# USB_SERIAL.net
KiCad netlist of a schematic drawn in Altium Designer
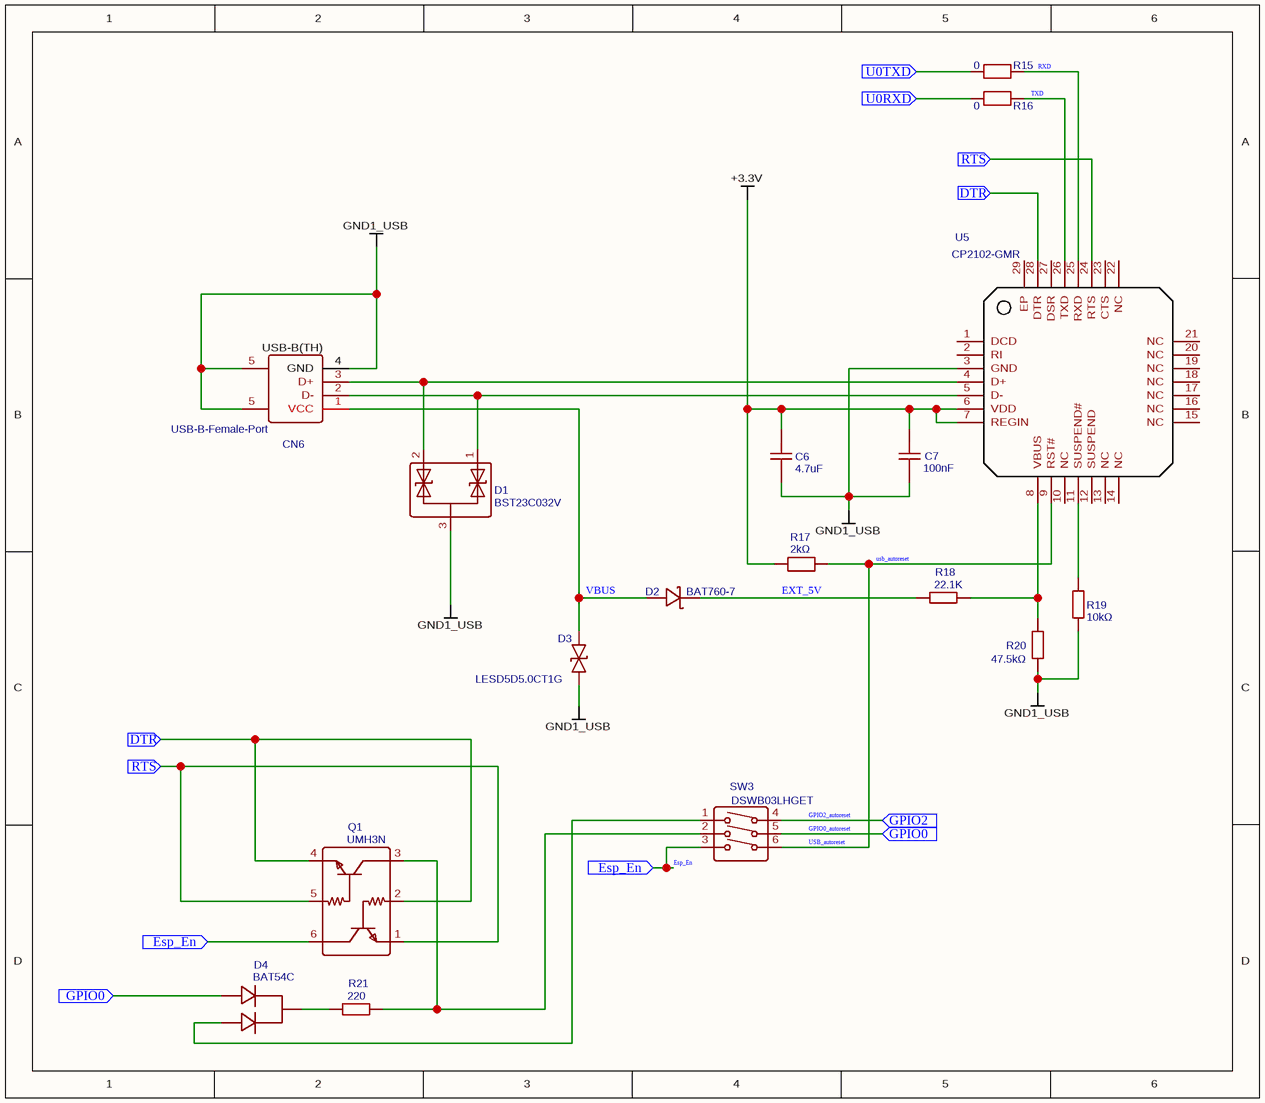
[diagram p0: USB_SERIAL.schdoc]

(export (version "E")
  (design (tool "Eeschema 10.0.6"))
  (components
    (comp (ref "C6")
      (value "4.7uF")
      (fields
        (field (name "BOM_SUPPLIER PART") "C140692")
        (field (name "BOM_MANUFACTURER PART") "CL21A475KQFNNNE")
        (field (name "CONTRIBUTOR") "LCSC")
      )
      (libsource (lib "altium-import") (part "root_1_4.7uF_"))
    )
    (comp (ref "C7")
      (value "100nF")
      (fields
        (field (name "BOM_SUPPLIER PART") "C519981")
        (field (name "BOM_MANUFACTURER PART") "CC0805KRX7R8BB104")
        (field (name "CONTRIBUTOR") "LCSC")
      )
      (libsource (lib "altium-import") (part "root_1_100nF_"))
    )
    (comp (ref "CN6")
      (value "USB-B-Female-Port")
      (fields
        (field (name "BOM_MANUFACTURER PART") "921-112A1010D10200")
        (field (name "BOM_SUPPLIER PART") "C46393")
      )
      (libsource (lib "altium-import") (part "root_0_USB-B-Female-Port_"))
    )
    (comp (ref "D1")
      (value "BST23C032V")
      (fields (field (name "BOM_SUPPLIER PART") "C151968") (field (name "CONTRIBUTOR") "LCSC"))
      (libsource (lib "altium-import") (part "root_2_BST23C032V_"))
    )
    (comp (ref "D2")
      (value "BAT760-7")
      (fields (field (name "BOM_SUPPLIER PART") "C124187") (field (name "CONTRIBUTOR") "LCSC"))
      (libsource (lib "altium-import") (part "root_2_BAT760-7_"))
    )
    (comp (ref "D3")
      (value "LESD5D5.0CT1G")
      (fields (field (name "BOM_SUPPLIER PART") "C383211") (field (name "CONTRIBUTOR") "LCSC"))
      (libsource (lib "altium-import") (part "root_1_LESD5D5.0CT1G_"))
    )
    (comp (ref "D4")
      (value "BAT54C")
      (fields (field (name "BOM_SUPPLIER PART") "C2135"))
      (libsource (lib "altium-import") (part "root_0_BAT54C_"))
    )
    (comp (ref "Q1")
      (value "UMH3N")
      (fields (field (name "BOM_SUPPLIER PART") "C62892"))
      (libsource (lib "altium-import") (part "root_1_UMH3N_"))
    )
    (comp (ref "R15")
      (value "0")
      (fields
        (field (name "BOM_SUPPLIER PART") "C174076")
        (field (name "BOM_MANUFACTURER PART") "AC0805FR-070RL")
        (field (name "CONTRIBUTOR") "LCSC")
      )
      (libsource (lib "altium-import") (part "root_0_0_"))
    )
    (comp (ref "R16")
      (value "0")
      (fields
        (field (name "BOM_SUPPLIER PART") "C174076")
        (field (name "BOM_MANUFACTURER PART") "AC0805FR-070RL")
        (field (name "CONTRIBUTOR") "LCSC")
      )
      (libsource (lib "altium-import") (part "root_0_0_"))
    )
    (comp (ref "R17")
      (value "2kΩ")
      (fields
        (field (name "BOM_SUPPLIER PART") "C479096")
        (field (name "BOM_MANUFACTURER PART") "PTFR0805B2K00P9")
        (field (name "CONTRIBUTOR") "LCSC")
      )
      (libsource (lib "altium-import") (part "root_0_2kΩ_"))
    )
    (comp (ref "R18")
      (value "22.1K")
      (fields
        (field (name "BOM_SUPPLIER PART") "C204311")
        (field (name "BOM_MANUFACTURER PART") "CR0805-FX-2212ELF")
        (field (name "CONTRIBUTOR") "LCSC")
      )
      (libsource (lib "altium-import") (part "root_0_22.1K_"))
    )
    (comp (ref "R19")
      (value "10kΩ")
      (fields
        (field (name "BOM_SUPPLIER PART") "C332266")
        (field (name "BOM_MANUFACTURER PART") "TR0805D10KP0550")
        (field (name "CONTRIBUTOR") "LCSC")
      )
      (libsource (lib "altium-import") (part "root_1_10kΩ_"))
    )
    (comp (ref "R20")
      (value "47.5kΩ")
      (fields
        (field (name "BOM_SUPPLIER PART") "C79481")
        (field (name "BOM_MANUFACTURER PART") "TC0525B4752T5E")
        (field (name "CONTRIBUTOR") "LCSC")
      )
      (libsource (lib "altium-import") (part "root_1_47.5kΩ_"))
    )
    (comp (ref "R21")
      (value "220")
      (fields
        (field (name "BOM_MANUFACTURER PART") "RC0805JR-7W220RL")
        (field (name "BOM_SUPPLIER PART") "C163392")
        (field (name "CONTRIBUTOR") "LCSC")
      )
      (libsource (lib "altium-import") (part "root_2_220_"))
    )
    (comp (ref "SW3")
      (value "DSWB03LHGET")
      (fields (field (name "BOM_SUPPLIER PART") "C99420") (field (name "CONTRIBUTOR") "LCSC"))
      (libsource (lib "altium-import") (part "root_3_DSWB03LHGET_"))
    )
    (comp (ref "U5")
      (value "CP2102-GMR")
      (fields (field (name "BOM_SUPPLIER PART") "C6568"))
      (libsource (lib "altium-import") (part "root_0_CP2102-GMR_"))
    )
  )
  (nets
    (net (code "1") (name "+3.3V") (class "Default")
      (node (ref "C6") (pin "2") (pinfunction "2_2") (pintype "passive"))
      (node (ref "C7") (pin "2") (pinfunction "2_2") (pintype "passive"))
      (node (ref "R17") (pin "1") (pinfunction "1_1") (pintype "passive"))
      (node (ref "U5") (pin "6") (pinfunction "VDD_6") (pintype "passive"))
      (node (ref "U5") (pin "7") (pinfunction "REGIN_7") (pintype "passive"))
    )
    (net (code "2") (name "/DTR") (class "Default")
      (node (ref "Q1") (pin "2") (pinfunction "B_2") (pintype "passive"))
      (node (ref "Q1") (pin "4") (pinfunction "E_4") (pintype "passive"))
      (node (ref "U5") (pin "28") (pinfunction "DTR_28") (pintype "passive"))
    )
    (net (code "3") (name "/EXT_5V") (class "Default")
      (node (ref "D2") (pin "1") (pinfunction "1_1") (pintype "passive"))
      (node (ref "R18") (pin "1") (pinfunction "1_1") (pintype "passive"))
    )
    (net (code "4") (name "/Esp_En") (class "Default")
      (node (ref "Q1") (pin "6") (pinfunction "C_6") (pintype "passive"))
      (node (ref "SW3") (pin "3") (pinfunction "3_3") (pintype "passive"))
    )
    (net (code "5") (name "/GPIO0_autoreset") (class "Default")
      (node (ref "D4") (pin "1") (pinfunction "A1_1") (pintype "passive"))
      (node (ref "SW3") (pin "5") (pinfunction "5_5") (pintype "passive"))
    )
    (net (code "6") (name "/GPIO2_autoreset") (class "Default")
      (node (ref "SW3") (pin "4") (pinfunction "4_4") (pintype "passive"))
    )
    (net (code "7") (name "/RTS") (class "Default")
      (node (ref "Q1") (pin "1") (pinfunction "E_1") (pintype "passive"))
      (node (ref "Q1") (pin "5") (pinfunction "B_5") (pintype "passive"))
      (node (ref "U5") (pin "24") (pinfunction "RTS_24") (pintype "passive"))
    )
    (net (code "8") (name "/RXD") (class "Default")
      (node (ref "R15") (pin "2") (pinfunction "2_2") (pintype "passive"))
      (node (ref "U5") (pin "25") (pinfunction "RXD_25") (pintype "passive"))
    )
    (net (code "9") (name "/TXD") (class "Default")
      (node (ref "R16") (pin "2") (pinfunction "2_2") (pintype "passive"))
      (node (ref "U5") (pin "26") (pinfunction "TXD_26") (pintype "passive"))
    )
    (net (code "10") (name "/U0RXD") (class "Default")
      (node (ref "R16") (pin "1") (pinfunction "1_1") (pintype "passive"))
    )
    (net (code "11") (name "/U0TXD") (class "Default")
      (node (ref "R15") (pin "1") (pinfunction "1_1") (pintype "passive"))
    )
    (net (code "12") (name "/USB_autoreset") (class "Default")
      (node (ref "R17") (pin "2") (pinfunction "2_2") (pintype "passive"))
      (node (ref "SW3") (pin "6") (pinfunction "6_6") (pintype "passive"))
      (node (ref "U5") (pin "9") (pinfunction "RST#_9") (pintype "passive"))
    )
    (net (code "13") (name "/VBUS") (class "Default")
      (node (ref "CN6") (pin "1") (pinfunction "VCC_1") (pintype "passive"))
      (node (ref "D2") (pin "2") (pinfunction "2_2") (pintype "passive"))
      (node (ref "D3") (pin "2") (pinfunction "2_2") (pintype "passive"))
    )
    (net (code "14") (name "GND1_USB") (class "Default")
      (node (ref "C6") (pin "1") (pinfunction "1_1") (pintype "passive"))
      (node (ref "C7") (pin "1") (pinfunction "1_1") (pintype "passive"))
      (node (ref "CN6") (pin "4") (pinfunction "GND_4") (pintype "passive"))
      (node (ref "CN6") (pin "5") (pinfunction "EH_5") (pintype "passive"))
      (node (ref "D1") (pin "3") (pinfunction "3_3") (pintype "passive"))
      (node (ref "D3") (pin "1") (pinfunction "1_1") (pintype "passive"))
      (node (ref "R19") (pin "1") (pinfunction "1_1") (pintype "passive"))
      (node (ref "R20") (pin "1") (pinfunction "1_1") (pintype "passive"))
      (node (ref "U5") (pin "3") (pinfunction "GND_3") (pintype "passive"))
    )
    (net (code "15") (name "Net-(CN6-D+)") (class "Default")
      (node (ref "CN6") (pin "3") (pinfunction "D+_3") (pintype "passive"))
      (node (ref "D1") (pin "2") (pinfunction "2_2") (pintype "passive"))
      (node (ref "U5") (pin "4") (pinfunction "D+_4") (pintype "passive"))
    )
    (net (code "16") (name "Net-(CN6-D-)") (class "Default")
      (node (ref "CN6") (pin "2") (pinfunction "D-_2") (pintype "passive"))
      (node (ref "D1") (pin "1") (pinfunction "1_1") (pintype "passive"))
      (node (ref "U5") (pin "5") (pinfunction "D-_5") (pintype "passive"))
    )
    (net (code "17") (name "Net-(D4-A2)") (class "Default")
      (node (ref "D4") (pin "2") (pinfunction "A2_2") (pintype "passive"))
      (node (ref "SW3") (pin "1") (pinfunction "1_1") (pintype "passive"))
    )
    (net (code "18") (name "Net-(D4-K)") (class "Default")
      (node (ref "D4") (pin "3") (pinfunction "K_3") (pintype "passive"))
      (node (ref "R21") (pin "2") (pinfunction "2_2") (pintype "passive"))
    )
    (net (code "19") (name "Net-(Q1-C-Pad3)") (class "Default")
      (node (ref "Q1") (pin "3") (pinfunction "C_3") (pintype "passive"))
      (node (ref "R21") (pin "1") (pinfunction "1_1") (pintype "passive"))
      (node (ref "SW3") (pin "2") (pinfunction "2_2") (pintype "passive"))
    )
    (net (code "20") (name "Net-(U5-SUSPEND#)") (class "Default")
      (node (ref "R19") (pin "2") (pinfunction "2_2") (pintype "passive"))
      (node (ref "U5") (pin "11") (pinfunction "SUSPEND#_11") (pintype "passive"))
    )
    (net (code "21") (name "Net-(U5-VBUS)") (class "Default")
      (node (ref "R18") (pin "2") (pinfunction "2_2") (pintype "passive"))
      (node (ref "R20") (pin "2") (pinfunction "2_2") (pintype "passive"))
      (node (ref "U5") (pin "8") (pinfunction "VBUS_8") (pintype "passive"))
    )
    (net (code "22") (name "unconnected-(U5-CTS-Pad23)") (class "Default")
      (node (ref "U5") (pin "23") (pinfunction "CTS_23") (pintype "passive"))
    )
    (net (code "23") (name "unconnected-(U5-DCD-Pad1)") (class "Default")
      (node (ref "U5") (pin "1") (pinfunction "DCD_1") (pintype "passive"))
    )
    (net (code "24") (name "unconnected-(U5-DSR-Pad27)") (class "Default")
      (node (ref "U5") (pin "27") (pinfunction "DSR_27") (pintype "passive"))
    )
    (net (code "25") (name "unconnected-(U5-EP-Pad29)") (class "Default")
      (node (ref "U5") (pin "29") (pinfunction "EP_29") (pintype "passive"))
    )
    (net (code "26") (name "unconnected-(U5-NC-Pad10)") (class "Default")
      (node (ref "U5") (pin "10") (pinfunction "NC_10") (pintype "passive"))
    )
    (net (code "27") (name "unconnected-(U5-NC-Pad13)") (class "Default")
      (node (ref "U5") (pin "13") (pinfunction "NC_13") (pintype "passive"))
    )
    (net (code "28") (name "unconnected-(U5-NC-Pad14)") (class "Default")
      (node (ref "U5") (pin "14") (pinfunction "NC_14") (pintype "passive"))
    )
    (net (code "29") (name "unconnected-(U5-NC-Pad15)") (class "Default")
      (node (ref "U5") (pin "15") (pinfunction "NC_15") (pintype "passive"))
    )
    (net (code "30") (name "unconnected-(U5-NC-Pad16)") (class "Default")
      (node (ref "U5") (pin "16") (pinfunction "NC_16") (pintype "passive"))
    )
    (net (code "31") (name "unconnected-(U5-NC-Pad17)") (class "Default")
      (node (ref "U5") (pin "17") (pinfunction "NC_17") (pintype "passive"))
    )
    (net (code "32") (name "unconnected-(U5-NC-Pad18)") (class "Default")
      (node (ref "U5") (pin "18") (pinfunction "NC_18") (pintype "passive"))
    )
    (net (code "33") (name "unconnected-(U5-NC-Pad19)") (class "Default")
      (node (ref "U5") (pin "19") (pinfunction "NC_19") (pintype "passive"))
    )
    (net (code "34") (name "unconnected-(U5-NC-Pad20)") (class "Default")
      (node (ref "U5") (pin "20") (pinfunction "NC_20") (pintype "passive"))
    )
    (net (code "35") (name "unconnected-(U5-NC-Pad21)") (class "Default")
      (node (ref "U5") (pin "21") (pinfunction "NC_21") (pintype "passive"))
    )
    (net (code "36") (name "unconnected-(U5-NC-Pad22)") (class "Default")
      (node (ref "U5") (pin "22") (pinfunction "NC_22") (pintype "passive"))
    )
    (net (code "37") (name "unconnected-(U5-RI-Pad2)") (class "Default")
      (node (ref "U5") (pin "2") (pinfunction "RI_2") (pintype "passive"))
    )
    (net (code "38") (name "unconnected-(U5-SUSPEND-Pad12)") (class "Default")
      (node (ref "U5") (pin "12") (pinfunction "SUSPEND_12") (pintype "passive"))
    )
  )
)
